# Sheet_EPM7064SLC44.net
KiCad netlist of a schematic drawn in Altium Designer
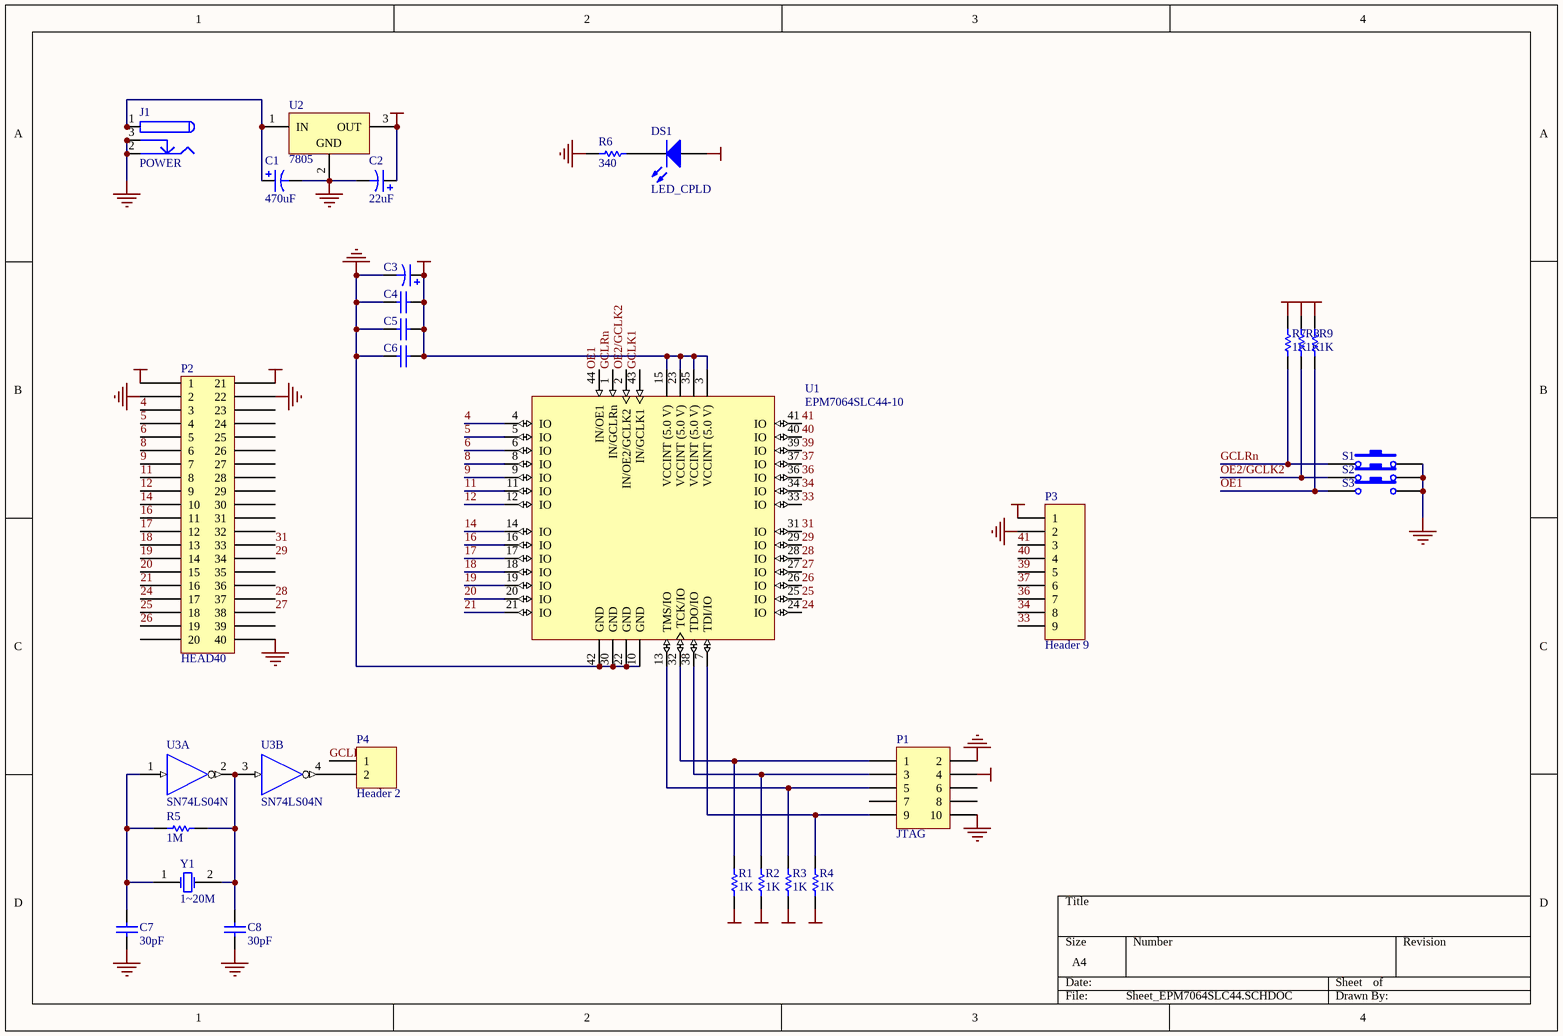
[diagram p0: Sheet_EPM7064SLC44.SCHDOC]

(export (version "E")
  (design (tool "Eeschema 10.0.6"))
  (components
    (comp (ref "C1")
      (value "470uF")
      (footprint "CAPPR2-5x6.8")
      (description "Polarized Capacitor (Radial)")
      (fields (field (name "PUBLISHER") "Altium Limited"))
      (libsource (lib "Miscellaneous Devices") (part "Cap Pol1"))
    )
    (comp (ref "C2")
      (value "22uF")
      (footprint "CAPPR1.5-4x5")
      (description "Polarized Capacitor (Radial)")
      (fields (field (name "PUBLISHER") "Altium Limited"))
      (libsource (lib "Miscellaneous Devices") (part "Cap Pol1"))
    )
    (comp (ref "C3")
      (value "10uF")
      (footprint "CAPPR1.5-4x5")
      (description "Polarized Capacitor (Radial)")
      (fields (field (name "PUBLISHER") "Altium Limited"))
      (libsource (lib "Miscellaneous Devices") (part "Cap Pol1"))
    )
    (comp (ref "C4")
      (value "0.1uF")
      (footprint "CAPR2.54-5.1x3.2")
      (description "Capacitor")
      (fields (field (name "PUBLISHER") "Altium Limited"))
      (libsource (lib "Miscellaneous Devices") (part "Cap"))
    )
    (comp (ref "C5")
      (value "0.1uF")
      (footprint "CAPR2.54-5.1x3.2")
      (description "Capacitor")
      (fields (field (name "PUBLISHER") "Altium Limited"))
      (libsource (lib "Miscellaneous Devices") (part "Cap"))
    )
    (comp (ref "C6")
      (value "0.1uF")
      (footprint "CAPR2.54-5.1x3.2")
      (description "Capacitor")
      (fields (field (name "PUBLISHER") "Altium Limited"))
      (libsource (lib "Miscellaneous Devices") (part "Cap"))
    )
    (comp (ref "C7")
      (value "30pF")
      (footprint "CAPR2.54-5.1x3.2")
      (description "Capacitor")
      (fields (field (name "PUBLISHER") "Altium Limited"))
      (libsource (lib "Miscellaneous Devices") (part "Cap"))
    )
    (comp (ref "C8")
      (value "30pF")
      (footprint "CAPR2.54-5.1x3.2")
      (description "Capacitor")
      (fields (field (name "PUBLISHER") "Altium Limited"))
      (libsource (lib "Miscellaneous Devices") (part "Cap"))
    )
    (comp (ref "DS1")
      (value "LED_CPLD")
      (footprint "LED")
      (description "Typical INFRARED GaAs LED")
      (fields (field (name "PUBLISHER") "Altium Limited"))
      (libsource (lib "Integrated_Library_1") (part "LED0"))
    )
    (comp (ref "J1")
      (value "POWER")
      (footprint "KLD-0202")
      (description "Low Voltage Power Supply Connector")
      (fields (field (name "PUBLISHER") "Altium Limited"))
      (libsource (lib "Miscellaneous Connectors") (part "PWR2.5"))
    )
    (comp (ref "P1")
      (value "JTAG")
      (footprint "HEADER-5X2POL")
      (description "Header, 5-Pin, Dual row")
      (fields (field (name "PUBLISHER") "Altium Limited"))
      (libsource (lib "Integrated_Library_1") (part "Header 5X2"))
    )
    (comp (ref "P2")
      (value "HEAD40")
      (footprint "DBZ2")
      (libsource (lib "Integrated_Library_1") (part "HEAD40"))
    )
    (comp (ref "P3")
      (value "Header 9")
      (footprint "HDR1X9")
      (description "Header, 9-Pin")
      (fields (field (name "PUBLISHER") "Altium Limited"))
      (libsource (lib "Miscellaneous Connectors") (part "Header 9"))
    )
    (comp (ref "P4")
      (value "Header 2")
      (footprint "HDR1X2")
      (description "Header, 2-Pin")
      (fields (field (name "PUBLISHER") "Altium Limited"))
      (libsource (lib "Miscellaneous Connectors") (part "Header 2"))
    )
    (comp (ref "R1")
      (value "1K")
      (footprint "AXIAL-0.3")
      (description "Resistor")
      (fields (field (name "PUBLISHER") "Altium Limited"))
      (libsource (lib "Miscellaneous Devices") (part "Res1"))
    )
    (comp (ref "R2")
      (value "1K")
      (footprint "AXIAL-0.3")
      (description "Resistor")
      (fields (field (name "PUBLISHER") "Altium Limited"))
      (libsource (lib "Miscellaneous Devices") (part "Res1"))
    )
    (comp (ref "R3")
      (value "1K")
      (footprint "AXIAL-0.3")
      (description "Resistor")
      (fields (field (name "PUBLISHER") "Altium Limited"))
      (libsource (lib "Miscellaneous Devices") (part "Res1"))
    )
    (comp (ref "R4")
      (value "1K")
      (footprint "AXIAL-0.3")
      (description "Resistor")
      (fields (field (name "PUBLISHER") "Altium Limited"))
      (libsource (lib "Miscellaneous Devices") (part "Res1"))
    )
    (comp (ref "R5")
      (value "1M")
      (footprint "AXIAL-0.3")
      (description "Resistor")
      (fields (field (name "PUBLISHER") "Altium Limited"))
      (libsource (lib "Miscellaneous Devices") (part "Res1"))
    )
    (comp (ref "R6")
      (value "340")
      (footprint "AXIAL-0.3")
      (description "Resistor")
      (fields (field (name "PUBLISHER") "Altium Limited"))
      (libsource (lib "Miscellaneous Devices") (part "Res1"))
    )
    (comp (ref "R7")
      (value "1K")
      (footprint "AXIAL-0.3")
      (description "Resistor")
      (fields (field (name "PUBLISHER") "Altium Limited"))
      (libsource (lib "Miscellaneous Devices") (part "Res1"))
    )
    (comp (ref "R8")
      (value "1K")
      (footprint "AXIAL-0.3")
      (description "Resistor")
      (fields (field (name "PUBLISHER") "Altium Limited"))
      (libsource (lib "Miscellaneous Devices") (part "Res1"))
    )
    (comp (ref "R9")
      (value "1K")
      (footprint "AXIAL-0.3")
      (description "Resistor")
      (fields (field (name "PUBLISHER") "Altium Limited"))
      (libsource (lib "Miscellaneous Devices") (part "Res1"))
    )
    (comp (ref "S1")
      (value "SW-PB")
      (footprint "SPST-2")
      (description "Switch")
      (fields (field (name "PUBLISHER") "Altium Limited"))
      (libsource (lib "Miscellaneous Devices") (part "SW-PB"))
    )
    (comp (ref "S2")
      (value "SW-PB")
      (footprint "SPST-2")
      (description "Switch")
      (fields (field (name "PUBLISHER") "Altium Limited"))
      (libsource (lib "Miscellaneous Devices") (part "SW-PB"))
    )
    (comp (ref "S3")
      (value "SW-PB")
      (footprint "SPST-2")
      (description "Switch")
      (fields (field (name "PUBLISHER") "Altium Limited"))
      (libsource (lib "Miscellaneous Devices") (part "SW-PB"))
    )
    (comp (ref "U1")
      (value "EPM7064SLC44-10")
      (footprint "PLCC_44")
      (fields (field (name "PUBLISHER") "Altium Limited"))
      (libsource (lib "Integrated_Library_1") (part "EPM7064SLC44-10"))
    )
    (comp (ref "U2")
      (value "7805")
      (footprint "KC03")
      (description "3-Terminal Positive Regulator")
      (fields (field (name "PUBLISHER") "Altium Limited"))
      (libsource (lib "TI Power Mgt Voltage Regulator") (part "LM330KC"))
    )
    (comp (ref "U3")
      (value "SN74LS04N")
      (footprint "N014")
      (description "Hex Inverter")
      (fields (field (name "PUBLISHER") "Altium Limited"))
      (libsource (lib "TI Logic Gate 2") (part "SN74LS04N"))
    )
    (comp (ref "Y1")
      (value "1~20M")
      (footprint "XT2")
      (description "Crystal Oscillator")
      (fields (field (name "PUBLISHER") "Altium Limited"))
      (libsource (lib "Integrated_Library_1") (part "XTAL"))
    )
  )
  (nets
    (net (code "1") (name "/4") (class "Default")
      (node (ref "P2") (pin "3") (pinfunction "3_3") (pintype "passive"))
      (node (ref "U1") (pin "4") (pinfunction "IO_4") (pintype "bidirectional"))
    )
    (net (code "2") (name "/5") (class "Default")
      (node (ref "P2") (pin "4") (pinfunction "4_4") (pintype "passive"))
      (node (ref "U1") (pin "5") (pinfunction "IO_5") (pintype "bidirectional"))
    )
    (net (code "3") (name "/6") (class "Default")
      (node (ref "P2") (pin "5") (pinfunction "5_5") (pintype "passive"))
      (node (ref "U1") (pin "6") (pinfunction "IO_6") (pintype "bidirectional"))
    )
    (net (code "4") (name "/8") (class "Default")
      (node (ref "P2") (pin "6") (pinfunction "6_6") (pintype "passive"))
      (node (ref "U1") (pin "8") (pinfunction "IO_8") (pintype "bidirectional"))
    )
    (net (code "5") (name "/9") (class "Default")
      (node (ref "P2") (pin "7") (pinfunction "7_7") (pintype "passive"))
      (node (ref "U1") (pin "9") (pinfunction "IO_9") (pintype "bidirectional"))
    )
    (net (code "6") (name "/11") (class "Default")
      (node (ref "P2") (pin "8") (pinfunction "8_8") (pintype "passive"))
      (node (ref "U1") (pin "11") (pinfunction "IO_11") (pintype "bidirectional"))
    )
    (net (code "7") (name "/12") (class "Default")
      (node (ref "P2") (pin "9") (pinfunction "9_9") (pintype "passive"))
      (node (ref "U1") (pin "12") (pinfunction "IO_12") (pintype "bidirectional"))
    )
    (net (code "8") (name "/14") (class "Default")
      (node (ref "P2") (pin "10") (pinfunction "10_10") (pintype "passive"))
      (node (ref "U1") (pin "14") (pinfunction "IO_14") (pintype "bidirectional"))
    )
    (net (code "9") (name "/16") (class "Default")
      (node (ref "P2") (pin "11") (pinfunction "11_11") (pintype "passive"))
      (node (ref "U1") (pin "16") (pinfunction "IO_16") (pintype "bidirectional"))
    )
    (net (code "10") (name "/17") (class "Default")
      (node (ref "P2") (pin "12") (pinfunction "12_12") (pintype "passive"))
      (node (ref "U1") (pin "17") (pinfunction "IO_17") (pintype "bidirectional"))
    )
    (net (code "11") (name "/18") (class "Default")
      (node (ref "P2") (pin "13") (pinfunction "13_13") (pintype "passive"))
      (node (ref "U1") (pin "18") (pinfunction "IO_18") (pintype "bidirectional"))
    )
    (net (code "12") (name "/19") (class "Default")
      (node (ref "P2") (pin "14") (pinfunction "14_14") (pintype "passive"))
      (node (ref "U1") (pin "19") (pinfunction "IO_19") (pintype "bidirectional"))
    )
    (net (code "13") (name "/20") (class "Default")
      (node (ref "P2") (pin "15") (pinfunction "15_15") (pintype "passive"))
      (node (ref "U1") (pin "20") (pinfunction "IO_20") (pintype "bidirectional"))
    )
    (net (code "14") (name "/21") (class "Default")
      (node (ref "P2") (pin "16") (pinfunction "16_16") (pintype "passive"))
      (node (ref "U1") (pin "21") (pinfunction "IO_21") (pintype "bidirectional"))
    )
    (net (code "15") (name "/24") (class "Default")
      (node (ref "P2") (pin "17") (pinfunction "17_17") (pintype "passive"))
      (node (ref "U1") (pin "24") (pinfunction "IO_24") (pintype "bidirectional"))
    )
    (net (code "16") (name "/25") (class "Default")
      (node (ref "P2") (pin "18") (pinfunction "18_18") (pintype "passive"))
      (node (ref "U1") (pin "25") (pinfunction "IO_25") (pintype "bidirectional"))
    )
    (net (code "17") (name "/26") (class "Default")
      (node (ref "P2") (pin "19") (pinfunction "19_19") (pintype "passive"))
      (node (ref "U1") (pin "26") (pinfunction "IO_26") (pintype "bidirectional"))
    )
    (net (code "18") (name "/27") (class "Default")
      (node (ref "P2") (pin "38") (pinfunction "38_38") (pintype "passive"))
      (node (ref "U1") (pin "27") (pinfunction "IO_27") (pintype "bidirectional"))
    )
    (net (code "19") (name "/28") (class "Default")
      (node (ref "P2") (pin "37") (pinfunction "37_37") (pintype "passive"))
      (node (ref "U1") (pin "28") (pinfunction "IO_28") (pintype "bidirectional"))
    )
    (net (code "20") (name "/29") (class "Default")
      (node (ref "P2") (pin "34") (pinfunction "34_34") (pintype "passive"))
      (node (ref "U1") (pin "29") (pinfunction "IO_29") (pintype "bidirectional"))
    )
    (net (code "21") (name "/31") (class "Default")
      (node (ref "P2") (pin "33") (pinfunction "33_33") (pintype "passive"))
      (node (ref "U1") (pin "31") (pinfunction "IO_31") (pintype "bidirectional"))
    )
    (net (code "22") (name "/33") (class "Default")
      (node (ref "P3") (pin "9") (pinfunction "9_9") (pintype "passive"))
      (node (ref "U1") (pin "33") (pinfunction "IO_33") (pintype "bidirectional"))
    )
    (net (code "23") (name "/34") (class "Default")
      (node (ref "P3") (pin "8") (pinfunction "8_8") (pintype "passive"))
      (node (ref "U1") (pin "34") (pinfunction "IO_34") (pintype "bidirectional"))
    )
    (net (code "24") (name "/36") (class "Default")
      (node (ref "P3") (pin "7") (pinfunction "7_7") (pintype "passive"))
      (node (ref "U1") (pin "36") (pinfunction "IO_36") (pintype "bidirectional"))
    )
    (net (code "25") (name "/37") (class "Default")
      (node (ref "P3") (pin "6") (pinfunction "6_6") (pintype "passive"))
      (node (ref "U1") (pin "37") (pinfunction "IO_37") (pintype "bidirectional"))
    )
    (net (code "26") (name "/39") (class "Default")
      (node (ref "P3") (pin "5") (pinfunction "5_5") (pintype "passive"))
      (node (ref "U1") (pin "39") (pinfunction "IO_39") (pintype "bidirectional"))
    )
    (net (code "27") (name "/40") (class "Default")
      (node (ref "P3") (pin "4") (pinfunction "4_4") (pintype "passive"))
      (node (ref "U1") (pin "40") (pinfunction "IO_40") (pintype "bidirectional"))
    )
    (net (code "28") (name "/41") (class "Default")
      (node (ref "P3") (pin "3") (pinfunction "3_3") (pintype "passive"))
      (node (ref "U1") (pin "41") (pinfunction "IO_41") (pintype "bidirectional"))
    )
    (net (code "29") (name "/GCLK1") (class "Default")
      (node (ref "P4") (pin "1") (pinfunction "1_1") (pintype "passive"))
      (node (ref "U1") (pin "43") (pinfunction "IN/GCLK1_43") (pintype "input"))
    )
    (net (code "30") (name "/GCLRn") (class "Default")
      (node (ref "R7") (pin "1") (pinfunction "1_1") (pintype "passive"))
      (node (ref "S1") (pin "1") (pinfunction "1_1") (pintype "passive"))
      (node (ref "U1") (pin "1") (pinfunction "IN/GCLRn_1") (pintype "input"))
    )
    (net (code "31") (name "/OE1") (class "Default")
      (node (ref "R9") (pin "1") (pinfunction "1_1") (pintype "passive"))
      (node (ref "S3") (pin "1") (pinfunction "1_1") (pintype "passive"))
      (node (ref "U1") (pin "44") (pinfunction "IN/OE1_44") (pintype "input"))
    )
    (net (code "32") (name "/OE2{slash}GCLK2") (class "Default")
      (node (ref "R8") (pin "1") (pinfunction "1_1") (pintype "passive"))
      (node (ref "S2") (pin "1") (pinfunction "1_1") (pintype "passive"))
      (node (ref "U1") (pin "2") (pinfunction "IN/OE2/GCLK2_2") (pintype "input"))
    )
    (net (code "33") (name "GND") (class "Default")
      (node (ref "C1") (pin "2") (pinfunction "2_2") (pintype "passive"))
      (node (ref "C2") (pin "2") (pinfunction "2_2") (pintype "passive"))
      (node (ref "C3") (pin "2") (pinfunction "2_2") (pintype "passive"))
      (node (ref "C4") (pin "1") (pinfunction "1_1") (pintype "passive"))
      (node (ref "C5") (pin "1") (pinfunction "1_1") (pintype "passive"))
      (node (ref "C6") (pin "1") (pinfunction "1_1") (pintype "passive"))
      (node (ref "C7") (pin "1") (pinfunction "1_1") (pintype "passive"))
      (node (ref "C8") (pin "1") (pinfunction "1_1") (pintype "passive"))
      (node (ref "J1") (pin "2") (pinfunction "2_2") (pintype "power_in"))
      (node (ref "J1") (pin "2A") (pinfunction "2A_2A") (pintype "power_in"))
      (node (ref "J1") (pin "2B") (pinfunction "2B_2B") (pintype "power_in"))
      (node (ref "J1") (pin "3") (pinfunction "3_3") (pintype "power_in"))
      (node (ref "J1") (pin "3A") (pinfunction "3A_3A") (pintype "power_in"))
      (node (ref "J1") (pin "3B") (pinfunction "3B_3B") (pintype "power_in"))
      (node (ref "P1") (pin "10") (pinfunction "10_10") (pintype "passive"))
      (node (ref "P1") (pin "2") (pinfunction "2_2") (pintype "passive"))
      (node (ref "P2") (pin "2") (pinfunction "2_2") (pintype "passive"))
      (node (ref "P2") (pin "22") (pinfunction "22_22") (pintype "passive"))
      (node (ref "P2") (pin "40") (pinfunction "40_40") (pintype "passive"))
      (node (ref "P3") (pin "2") (pinfunction "2_2") (pintype "passive"))
      (node (ref "R6") (pin "2") (pinfunction "2_2") (pintype "passive"))
      (node (ref "S1") (pin "2") (pinfunction "2_2") (pintype "passive"))
      (node (ref "S2") (pin "2") (pinfunction "2_2") (pintype "passive"))
      (node (ref "S3") (pin "2") (pinfunction "2_2") (pintype "passive"))
      (node (ref "U1") (pin "10") (pinfunction "GND_10") (pintype "power_in"))
      (node (ref "U1") (pin "22") (pinfunction "GND_22") (pintype "power_in"))
      (node (ref "U1") (pin "30") (pinfunction "GND_30") (pintype "power_in"))
      (node (ref "U1") (pin "42") (pinfunction "GND_42") (pintype "power_in"))
      (node (ref "U2") (pin "2") (pinfunction "GND_2") (pintype "power_in"))
      (node (ref "U3") (pin "7") (pinfunction "GND_7") (pintype "power_in"))
    )
    (net (code "34") (name "Net-(DS1-K)") (class "Default")
      (node (ref "DS1") (pin "2") (pinfunction "K_2") (pintype "passive"))
      (node (ref "R6") (pin "1") (pinfunction "1_1") (pintype "passive"))
    )
    (net (code "35") (name "Net-(U1-TCK{slash}IO)") (class "Default")
      (node (ref "P1") (pin "1") (pinfunction "1_1") (pintype "passive"))
      (node (ref "R1") (pin "2") (pinfunction "2_2") (pintype "passive"))
      (node (ref "U1") (pin "32") (pinfunction "TCK/IO_32") (pintype "bidirectional"))
    )
    (net (code "36") (name "Net-(U1-TDI{slash}IO)") (class "Default")
      (node (ref "P1") (pin "9") (pinfunction "9_9") (pintype "passive"))
      (node (ref "R4") (pin "2") (pinfunction "2_2") (pintype "passive"))
      (node (ref "U1") (pin "7") (pinfunction "TDI/IO_7") (pintype "bidirectional"))
    )
    (net (code "37") (name "Net-(U1-TDO{slash}IO)") (class "Default")
      (node (ref "P1") (pin "3") (pinfunction "3_3") (pintype "passive"))
      (node (ref "R2") (pin "2") (pinfunction "2_2") (pintype "passive"))
      (node (ref "U1") (pin "38") (pinfunction "TDO/IO_38") (pintype "bidirectional"))
    )
    (net (code "38") (name "Net-(U1-TMS{slash}IO)") (class "Default")
      (node (ref "P1") (pin "5") (pinfunction "5_5") (pintype "passive"))
      (node (ref "R3") (pin "2") (pinfunction "2_2") (pintype "passive"))
      (node (ref "U1") (pin "13") (pinfunction "TMS/IO_13") (pintype "bidirectional"))
    )
    (net (code "39") (name "Net-(U2-IN)") (class "Default")
      (node (ref "C1") (pin "1") (pinfunction "1_1") (pintype "passive"))
      (node (ref "J1") (pin "1") (pinfunction "1_1") (pintype "power_in"))
      (node (ref "J1") (pin "1A") (pinfunction "1A_1A") (pintype "power_in"))
      (node (ref "J1") (pin "1B") (pinfunction "1B_1B") (pintype "power_in"))
      (node (ref "U2") (pin "1") (pinfunction "IN_1") (pintype "power_in"))
    )
    (net (code "40") (name "Net-(U3A-A)") (class "Default")
      (node (ref "C7") (pin "2") (pinfunction "2_2") (pintype "passive"))
      (node (ref "R5") (pin "1") (pinfunction "1_1") (pintype "passive"))
      (node (ref "U3") (pin "1") (pinfunction "A_1") (pintype "input"))
      (node (ref "Y1") (pin "1") (pinfunction "OSC1_1") (pintype "passive"))
    )
    (net (code "41") (name "Net-(U3A-Y)") (class "Default")
      (node (ref "C8") (pin "2") (pinfunction "2_2") (pintype "passive"))
      (node (ref "R5") (pin "2") (pinfunction "2_2") (pintype "passive"))
      (node (ref "U3") (pin "2") (pinfunction "Y_2") (pintype "output"))
      (node (ref "U3") (pin "3") (pinfunction "A_3") (pintype "input"))
      (node (ref "Y1") (pin "2") (pinfunction "OSC2_2") (pintype "passive"))
    )
    (net (code "42") (name "Net-(U3B-Y)") (class "Default")
      (node (ref "P4") (pin "2") (pinfunction "2_2") (pintype "passive"))
      (node (ref "U3") (pin "4") (pinfunction "Y_4") (pintype "output"))
    )
    (net (code "43") (name "VCC") (class "Default")
      (node (ref "C2") (pin "1") (pinfunction "1_1") (pintype "passive"))
      (node (ref "C3") (pin "1") (pinfunction "1_1") (pintype "passive"))
      (node (ref "C4") (pin "2") (pinfunction "2_2") (pintype "passive"))
      (node (ref "C5") (pin "2") (pinfunction "2_2") (pintype "passive"))
      (node (ref "C6") (pin "2") (pinfunction "2_2") (pintype "passive"))
      (node (ref "DS1") (pin "1") (pinfunction "A_1") (pintype "passive"))
      (node (ref "P1") (pin "4") (pinfunction "4_4") (pintype "passive"))
      (node (ref "P2") (pin "1") (pinfunction "1_1") (pintype "passive"))
      (node (ref "P2") (pin "21") (pinfunction "21_21") (pintype "passive"))
      (node (ref "P3") (pin "1") (pinfunction "1_1") (pintype "passive"))
      (node (ref "R1") (pin "1") (pinfunction "1_1") (pintype "passive"))
      (node (ref "R2") (pin "1") (pinfunction "1_1") (pintype "passive"))
      (node (ref "R3") (pin "1") (pinfunction "1_1") (pintype "passive"))
      (node (ref "R4") (pin "1") (pinfunction "1_1") (pintype "passive"))
      (node (ref "R7") (pin "2") (pinfunction "2_2") (pintype "passive"))
      (node (ref "R8") (pin "2") (pinfunction "2_2") (pintype "passive"))
      (node (ref "R9") (pin "2") (pinfunction "2_2") (pintype "passive"))
      (node (ref "U1") (pin "15") (pinfunction "VCCINT_(5.0_V)_15") (pintype "power_in"))
      (node (ref "U1") (pin "23") (pinfunction "VCCINT_(5.0_V)_23") (pintype "power_in"))
      (node (ref "U1") (pin "3") (pinfunction "VCCINT_(5.0_V)_3") (pintype "power_in"))
      (node (ref "U1") (pin "35") (pinfunction "VCCINT_(5.0_V)_35") (pintype "power_in"))
      (node (ref "U2") (pin "3") (pinfunction "OUT_3") (pintype "power_in"))
      (node (ref "U3") (pin "14") (pinfunction "VCC_14") (pintype "power_in"))
    )
    (net (code "44") (name "unconnected-(P1-Pad6)") (class "Default")
      (node (ref "P1") (pin "6") (pinfunction "6_6") (pintype "passive"))
    )
    (net (code "45") (name "unconnected-(P1-Pad7)") (class "Default")
      (node (ref "P1") (pin "7") (pinfunction "7_7") (pintype "passive"))
    )
    (net (code "46") (name "unconnected-(P1-Pad8)") (class "Default")
      (node (ref "P1") (pin "8") (pinfunction "8_8") (pintype "passive"))
    )
    (net (code "47") (name "unconnected-(P2-Pad20)") (class "Default")
      (node (ref "P2") (pin "20") (pinfunction "20_20") (pintype "passive"))
    )
    (net (code "48") (name "unconnected-(P2-Pad23)") (class "Default")
      (node (ref "P2") (pin "23") (pinfunction "23_23") (pintype "passive"))
    )
    (net (code "49") (name "unconnected-(P2-Pad24)") (class "Default")
      (node (ref "P2") (pin "24") (pinfunction "24_24") (pintype "passive"))
    )
    (net (code "50") (name "unconnected-(P2-Pad25)") (class "Default")
      (node (ref "P2") (pin "25") (pinfunction "25_25") (pintype "passive"))
    )
    (net (code "51") (name "unconnected-(P2-Pad26)") (class "Default")
      (node (ref "P2") (pin "26") (pinfunction "26_26") (pintype "passive"))
    )
    (net (code "52") (name "unconnected-(P2-Pad27)") (class "Default")
      (node (ref "P2") (pin "27") (pinfunction "27_27") (pintype "passive"))
    )
    (net (code "53") (name "unconnected-(P2-Pad28)") (class "Default")
      (node (ref "P2") (pin "28") (pinfunction "28_28") (pintype "passive"))
    )
    (net (code "54") (name "unconnected-(P2-Pad29)") (class "Default")
      (node (ref "P2") (pin "29") (pinfunction "29_29") (pintype "passive"))
    )
    (net (code "55") (name "unconnected-(P2-Pad30)") (class "Default")
      (node (ref "P2") (pin "30") (pinfunction "30_30") (pintype "passive"))
    )
    (net (code "56") (name "unconnected-(P2-Pad31)") (class "Default")
      (node (ref "P2") (pin "31") (pinfunction "31_31") (pintype "passive"))
    )
    (net (code "57") (name "unconnected-(P2-Pad32)") (class "Default")
      (node (ref "P2") (pin "32") (pinfunction "32_32") (pintype "passive"))
    )
    (net (code "58") (name "unconnected-(P2-Pad35)") (class "Default")
      (node (ref "P2") (pin "35") (pinfunction "35_35") (pintype "passive"))
    )
    (net (code "59") (name "unconnected-(P2-Pad36)") (class "Default")
      (node (ref "P2") (pin "36") (pinfunction "36_36") (pintype "passive"))
    )
    (net (code "60") (name "unconnected-(P2-Pad39)") (class "Default")
      (node (ref "P2") (pin "39") (pinfunction "39_39") (pintype "passive"))
    )
  )
)
